# ControlPCB_14042025.net
KiCad netlist of a schematic drawn in EAGLE
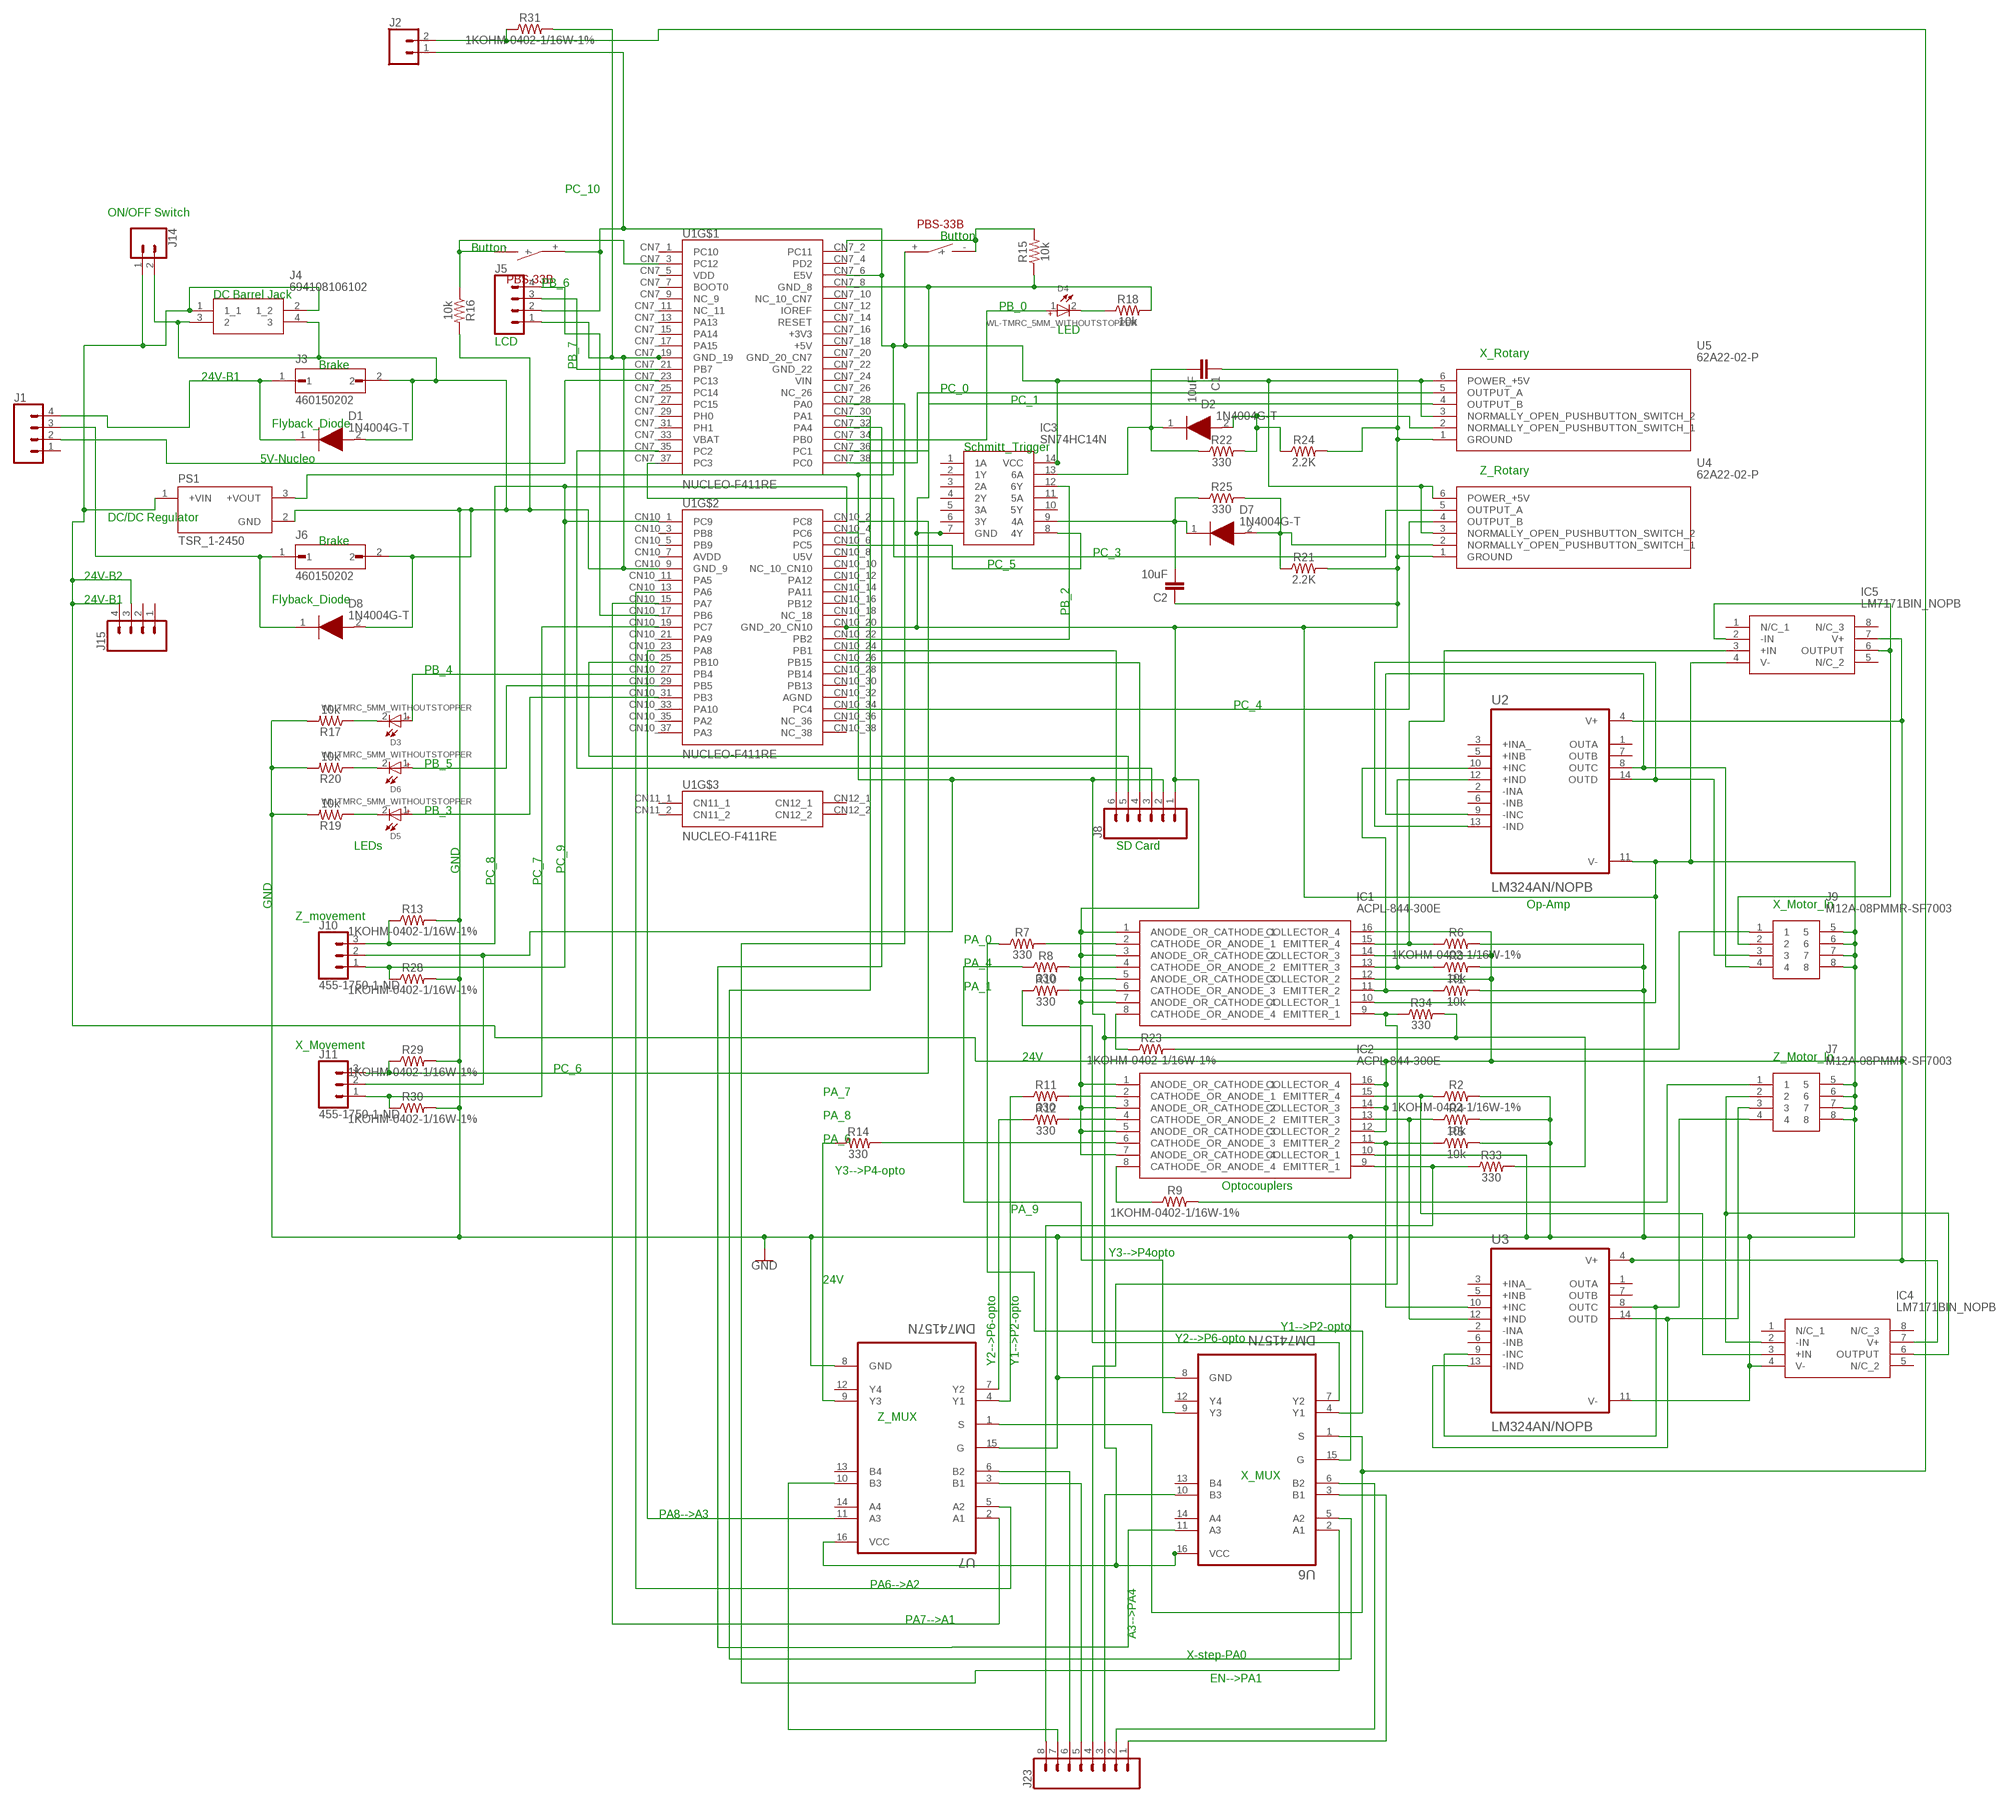
[diagram p0: schematic, sheet 1]

(export (version "E")
  (design (tool "Eeschema 10.0.6"))
  (components
    (comp (ref "C1")
      (value "10uF")
      (footprint "eagle-import:0603")
      (libsource (lib "eagle-import") (part "10UF-0603-6.3V-20%"))
    )
    (comp (ref "C2")
      (value "10uF")
      (footprint "eagle-import:0603")
      (libsource (lib "eagle-import") (part "10UF-0603-6.3V-20%"))
    )
    (comp (ref "D1")
      (value "1N4004G-T")
      (footprint "eagle-import:DIOAD1408W86L464D236")
      (fields (field (name "MOUSER_PART_NUMBER") "621-1N4004G-T"))
      (libsource (lib "eagle-import") (part "1N4004G-T"))
    )
    (comp (ref "D2")
      (value "1N4004G-T")
      (footprint "eagle-import:DIOAD1408W86L464D236")
      (fields (field (name "MOUSER_PART_NUMBER") "621-1N4004G-T"))
      (libsource (lib "eagle-import") (part "1N4004G-T"))
    )
    (comp (ref "D3")
      (value "WL-TMRC_5MM_WITHOUTSTOPPER")
      (footprint "eagle-import:WL-TMRC_5MM")
      (libsource (lib "eagle-import") (part "WL-TMRC_5MM_WITHOUTSTOPPER"))
    )
    (comp (ref "D4")
      (value "WL-TMRC_5MM_WITHOUTSTOPPER")
      (footprint "eagle-import:WL-TMRC_5MM")
      (libsource (lib "eagle-import") (part "WL-TMRC_5MM_WITHOUTSTOPPER"))
    )
    (comp (ref "D5")
      (value "WL-TMRC_5MM_WITHOUTSTOPPER")
      (footprint "eagle-import:WL-TMRC_5MM")
      (libsource (lib "eagle-import") (part "WL-TMRC_5MM_WITHOUTSTOPPER"))
    )
    (comp (ref "D6")
      (value "WL-TMRC_5MM_WITHOUTSTOPPER")
      (footprint "eagle-import:WL-TMRC_5MM")
      (libsource (lib "eagle-import") (part "WL-TMRC_5MM_WITHOUTSTOPPER"))
    )
    (comp (ref "D7")
      (value "1N4004G-T")
      (footprint "eagle-import:DIOAD1408W86L464D236")
      (fields (field (name "MOUSER_PART_NUMBER") "621-1N4004G-T"))
      (libsource (lib "eagle-import") (part "1N4004G-T"))
    )
    (comp (ref "D8")
      (value "1N4004G-T")
      (footprint "eagle-import:DIOAD1408W86L464D236")
      (fields (field (name "MOUSER_PART_NUMBER") "621-1N4004G-T"))
      (libsource (lib "eagle-import") (part "1N4004G-T"))
    )
    (comp (ref "IC1")
      (value "ACPL-844-300E")
      (footprint "eagle-import:DIP880W60P254L1984H450Q16N")
      (fields (field (name "MOUSER_PART_NUMBER") "630-ACPL-844-300E"))
      (libsource (lib "eagle-import") (part "ACPL-844-300E"))
    )
    (comp (ref "IC2")
      (value "ACPL-844-300E")
      (footprint "eagle-import:DIP880W60P254L1984H450Q16N")
      (fields (field (name "MOUSER_PART_NUMBER") "630-ACPL-844-300E"))
      (libsource (lib "eagle-import") (part "ACPL-844-300E"))
    )
    (comp (ref "IC3")
      (value "SN74HC14N")
      (footprint "eagle-import:DIP794W53P254L1930H508Q14N")
      (fields (field (name "MOUSER_PART_NUMBER") "595-SN74HC14N"))
      (libsource (lib "eagle-import") (part "SN74HC14N"))
    )
    (comp (ref "IC4")
      (value "LM7171BIN_NOPB")
      (footprint "eagle-import:DIP794W53P254L959H508Q8N")
      (fields
        (field (name "ARROW_PART_NUMBER") "LM7171BIN/NOPB")
        (field (name "MOUSER_PART_NUMBER") "926-LM7171BIN/NOPB")
      )
      (libsource (lib "eagle-import") (part "LM7171BIN_NOPB"))
    )
    (comp (ref "IC5")
      (value "LM7171BIN_NOPB")
      (footprint "eagle-import:DIP794W53P254L959H508Q8N")
      (fields
        (field (name "ARROW_PART_NUMBER") "LM7171BIN/NOPB")
        (field (name "MOUSER_PART_NUMBER") "926-LM7171BIN/NOPB")
      )
      (libsource (lib "eagle-import") (part "LM7171BIN_NOPB"))
    )
    (comp (ref "J1")
      (value "CONN_04PTH")
      (footprint "eagle-import:1X04")
      (libsource (lib "eagle-import") (part "CONN_04PTH"))
    )
    (comp (ref "J2")
      (value "CONN_02")
      (footprint "eagle-import:1X02")
      (libsource (lib "eagle-import") (part "CONN_02"))
    )
    (comp (ref "J3")
      (value "460150202")
      (footprint "eagle-import:MOLEX_460150202")
      (fields (field (name "MANUFACTURER") "Molex"))
      (libsource (lib "eagle-import") (part "460150202"))
    )
    (comp (ref "J4")
      (value "694108106102")
      (footprint "eagle-import:694108106102")
      (fields (field (name "MOUSER_PART_NUMBER") "710-694108106102"))
      (libsource (lib "eagle-import") (part "694108106102"))
    )
    (comp (ref "J5")
      (value "CONN_04LOCK")
      (footprint "eagle-import:1X04_LOCK")
      (libsource (lib "eagle-import") (part "CONN_04LOCK"))
    )
    (comp (ref "J6")
      (value "460150202")
      (footprint "eagle-import:MOLEX_460150202")
      (fields (field (name "MANUFACTURER") "Molex"))
      (libsource (lib "eagle-import") (part "460150202"))
    )
    (comp (ref "J7")
      (value "M12A-08PMMR-SF7003")
      (footprint "eagle-import:M12A08PMMRSF7003")
      (fields (field (name "MOUSER_PART_NUMBER") "523-M12A08PMMRSF7003"))
      (libsource (lib "eagle-import") (part "M12A-08PMMR-SF7003"))
    )
    (comp (ref "J8")
      (value "CONN_06SILK_FEMALE_PTH")
      (footprint "eagle-import:1X06")
      (libsource (lib "eagle-import") (part "CONN_06SILK_FEMALE_PTH"))
    )
    (comp (ref "J9")
      (value "M12A-08PMMR-SF7003")
      (footprint "eagle-import:M12A08PMMRSF7003")
      (fields (field (name "MOUSER_PART_NUMBER") "523-M12A08PMMRSF7003"))
      (libsource (lib "eagle-import") (part "M12A-08PMMR-SF7003"))
    )
    (comp (ref "J10")
      (value "455-1750-1-ND")
      (footprint "eagle-import:1X03")
      (libsource (lib "eagle-import") (part "CONN_03"))
    )
    (comp (ref "J11")
      (value "455-1750-1-ND")
      (footprint "eagle-import:1X03")
      (libsource (lib "eagle-import") (part "CONN_03"))
    )
    (comp (ref "J14")
      (value "CONN_02")
      (footprint "eagle-import:1X02")
      (libsource (lib "eagle-import") (part "CONN_02"))
    )
    (comp (ref "J15")
      (value "CONN_04PTH")
      (footprint "eagle-import:1X04")
      (libsource (lib "eagle-import") (part "CONN_04PTH"))
    )
    (comp (ref "J23")
      (value "CONN_08\"")
      (footprint "eagle-import:1X08")
      (libsource (lib "eagle-import") (part "CONN_08{dblquote}"))
    )
    (comp (ref "PS1")
      (value "TSR_1-2450")
      (footprint "eagle-import:CONV_TSR_1-2450")
      (fields (field (name "MANUFACTURER") "Traco Power"))
      (libsource (lib "eagle-import") (part "TSR_1-2450"))
    )
    (comp (ref "R1")
      (value "10k")
      (footprint "eagle-import:0402")
      (libsource (lib "eagle-import") (part "10KOHM-0402-1/16W-1%"))
    )
    (comp (ref "R2")
      (value "1KOHM-0402-1/16W-1%")
      (footprint "eagle-import:0402")
      (libsource (lib "eagle-import") (part "1KOHM-0402-1/16W-1%"))
    )
    (comp (ref "R3")
      (value "10k")
      (footprint "eagle-import:0402")
      (libsource (lib "eagle-import") (part "10KOHM-0402-1/16W-1%"))
    )
    (comp (ref "R4")
      (value "10k")
      (footprint "eagle-import:0402")
      (libsource (lib "eagle-import") (part "10KOHM-0402-1/16W-1%"))
    )
    (comp (ref "R5")
      (value "10k")
      (footprint "eagle-import:0402")
      (libsource (lib "eagle-import") (part "10KOHM-0402-1/16W-1%"))
    )
    (comp (ref "R6")
      (value "1KOHM-0402-1/16W-1%")
      (footprint "eagle-import:0402")
      (libsource (lib "eagle-import") (part "1KOHM-0402-1/16W-1%"))
    )
    (comp (ref "R7")
      (value "330")
      (footprint "eagle-import:0402")
      (libsource (lib "eagle-import") (part "330OHM-0402-1/16W-5%"))
    )
    (comp (ref "R8")
      (value "330")
      (footprint "eagle-import:0402")
      (libsource (lib "eagle-import") (part "330OHM-0402-1/16W-5%"))
    )
    (comp (ref "R9")
      (value "1KOHM-0402-1/16W-1%")
      (footprint "eagle-import:0402")
      (libsource (lib "eagle-import") (part "1KOHM-0402-1/16W-1%"))
    )
    (comp (ref "R10")
      (value "330")
      (footprint "eagle-import:0402")
      (libsource (lib "eagle-import") (part "330OHM-0402-1/16W-5%"))
    )
    (comp (ref "R11")
      (value "330")
      (footprint "eagle-import:0402")
      (libsource (lib "eagle-import") (part "330OHM-0402-1/16W-5%"))
    )
    (comp (ref "R12")
      (value "330")
      (footprint "eagle-import:0402")
      (libsource (lib "eagle-import") (part "330OHM-0402-1/16W-5%"))
    )
    (comp (ref "R13")
      (value "1KOHM-0402-1/16W-1%")
      (footprint "eagle-import:0402")
      (libsource (lib "eagle-import") (part "1KOHM-0402-1/16W-1%"))
    )
    (comp (ref "R14")
      (value "330")
      (footprint "eagle-import:0402")
      (libsource (lib "eagle-import") (part "330OHM-0402-1/16W-5%"))
    )
    (comp (ref "R15")
      (value "10k")
      (footprint "eagle-import:0402")
      (libsource (lib "eagle-import") (part "10KOHM-0402-1/16W-1%"))
    )
    (comp (ref "R16")
      (value "10k")
      (footprint "eagle-import:0402")
      (libsource (lib "eagle-import") (part "10KOHM-0402-1/16W-1%"))
    )
    (comp (ref "R17")
      (value "10k")
      (footprint "eagle-import:0402")
      (libsource (lib "eagle-import") (part "10KOHM-0402-1/16W-1%"))
    )
    (comp (ref "R18")
      (value "10k")
      (footprint "eagle-import:0402")
      (libsource (lib "eagle-import") (part "10KOHM-0402-1/16W-1%"))
    )
    (comp (ref "R19")
      (value "10k")
      (footprint "eagle-import:0402")
      (libsource (lib "eagle-import") (part "10KOHM-0402-1/16W-1%"))
    )
    (comp (ref "R20")
      (value "10k")
      (footprint "eagle-import:0402")
      (libsource (lib "eagle-import") (part "10KOHM-0402-1/16W-1%"))
    )
    (comp (ref "R21")
      (value "2.2K")
      (footprint "eagle-import:0402")
      (libsource (lib "eagle-import") (part "2.2KOHM-0402-1/16W-1%"))
    )
    (comp (ref "R22")
      (value "330")
      (footprint "eagle-import:0402")
      (libsource (lib "eagle-import") (part "330OHM-0402-1/16W-5%"))
    )
    (comp (ref "R23")
      (value "1KOHM-0402-1/16W-1%")
      (footprint "eagle-import:0402")
      (libsource (lib "eagle-import") (part "1KOHM-0402-1/16W-1%"))
    )
    (comp (ref "R24")
      (value "2.2K")
      (footprint "eagle-import:0402")
      (libsource (lib "eagle-import") (part "2.2KOHM-0402-1/16W-1%"))
    )
    (comp (ref "R25")
      (value "330")
      (footprint "eagle-import:0402")
      (libsource (lib "eagle-import") (part "330OHM-0402-1/16W-5%"))
    )
    (comp (ref "R28")
      (value "1KOHM-0402-1/16W-1%")
      (footprint "eagle-import:0402")
      (libsource (lib "eagle-import") (part "1KOHM-0402-1/16W-1%"))
    )
    (comp (ref "R29")
      (value "1KOHM-0402-1/16W-1%")
      (footprint "eagle-import:0402")
      (libsource (lib "eagle-import") (part "1KOHM-0402-1/16W-1%"))
    )
    (comp (ref "R30")
      (value "1KOHM-0402-1/16W-1%")
      (footprint "eagle-import:0402")
      (libsource (lib "eagle-import") (part "1KOHM-0402-1/16W-1%"))
    )
    (comp (ref "R31")
      (value "1KOHM-0402-1/16W-1%")
      (footprint "eagle-import:0402")
      (libsource (lib "eagle-import") (part "1KOHM-0402-1/16W-1%"))
    )
    (comp (ref "R33")
      (value "330")
      (footprint "eagle-import:0402")
      (libsource (lib "eagle-import") (part "330OHM-0402-1/16W-5%"))
    )
    (comp (ref "R34")
      (value "330")
      (footprint "eagle-import:0402")
      (libsource (lib "eagle-import") (part "330OHM-0402-1/16W-5%"))
    )
    (comp (ref "U$1")
      (value "PBS-33B")
      (footprint "eagle-import:PBS-33B")
      (libsource (lib "eagle-import") (part "PBS-33B"))
    )
    (comp (ref "U$2")
      (value "PBS-33B")
      (footprint "eagle-import:PBS-33B")
      (libsource (lib "eagle-import") (part "PBS-33B"))
    )
    (comp (ref "U1")
      (value "NUCLEO-F411RE")
      (footprint "eagle-import:BOARD_NUCLEO-F411RE")
      (fields (field (name "DIGIKEY_PART_NUMBER") "497-14711-ND") (field (name "MF") "STMicroelectronics"))
      (libsource (lib "eagle-import") (part "NUCLEO-F411RE"))
    )
    (comp (ref "U2")
      (value "LM324AN/NOPB")
      (footprint "eagle-import:DIP794W45P254L1969H508Q14")
      (libsource (lib "eagle-import") (part "LM324AN/NOPB"))
    )
    (comp (ref "U3")
      (value "LM324AN/NOPB")
      (footprint "eagle-import:DIP794W45P254L1969H508Q14")
      (libsource (lib "eagle-import") (part "LM324AN/NOPB"))
    )
    (comp (ref "U4")
      (value "62A22-02-P")
      (footprint "eagle-import:62A2202P")
      (fields (field (name "MOUSER_PART_NUMBER") "706-62A22-02-P"))
      (libsource (lib "eagle-import") (part "62A22-02-P"))
    )
    (comp (ref "U5")
      (value "62A22-02-P")
      (footprint "eagle-import:62A2202P")
      (fields (field (name "MOUSER_PART_NUMBER") "706-62A22-02-P"))
      (libsource (lib "eagle-import") (part "62A22-02-P"))
    )
    (comp (ref "U6")
      (value "DM74157N")
      (footprint "eagle-import:DIP794W45P254L1918H533Q16")
      (fields (field (name "MF") "ON Semiconductor"))
      (libsource (lib "eagle-import") (part "DM74157N"))
    )
    (comp (ref "U7")
      (value "DM74157N")
      (footprint "eagle-import:DIP794W45P254L1918H533Q16")
      (fields (field (name "MF") "ON Semiconductor"))
      (libsource (lib "eagle-import") (part "DM74157N"))
    )
  )
  (nets
    (net (code "1") (name "/+3V3") (class "Default")
      (node (ref "U1") (pin "CN7_16") (pinfunction "+3V3_CN7_16") (pintype "power_in"))
    )
    (net (code "2") (name "/+5V") (class "Default")
      (node (ref "U1") (pin "CN7_18") (pinfunction "+5V_CN7_18") (pintype "power_in"))
    )
    (net (code "3") (name "/AGND") (class "Default")
      (node (ref "U1") (pin "CN10_32") (pinfunction "AGND_CN10_32") (pintype "power_in"))
    )
    (net (code "4") (name "/AVDD") (class "Default")
      (node (ref "U1") (pin "CN10_7") (pinfunction "AVDD_CN10_7") (pintype "power_in"))
    )
    (net (code "5") (name "/GND_20_CN7") (class "Default")
      (node (ref "U1") (pin "CN7_20") (pinfunction "GND_20_CN7_CN7_20") (pintype "power_in"))
    )
    (net (code "6") (name "/GND_22") (class "Default")
      (node (ref "U1") (pin "CN7_22") (pinfunction "GND_22_CN7_22") (pintype "power_in"))
    )
    (net (code "7") (name "/U5V") (class "Default")
      (node (ref "U1") (pin "CN10_8") (pinfunction "U5V_CN10_8") (pintype "power_in"))
    )
    (net (code "8") (name "/VBAT") (class "Default")
      (node (ref "U1") (pin "CN7_33") (pinfunction "VBAT_CN7_33") (pintype "power_in"))
    )
    (net (code "9") (name "/VDD") (class "Default")
      (node (ref "U1") (pin "CN7_5") (pinfunction "VDD_CN7_5") (pintype "power_in"))
    )
    (net (code "10") (name "GND") (class "Default")
      (node (ref "C1") (pin "1") (pinfunction "1_1") (pintype "passive"))
      (node (ref "C2") (pin "1") (pinfunction "1_1") (pintype "passive"))
      (node (ref "D1") (pin "2") (pinfunction "A_2") (pintype "bidirectional"))
      (node (ref "D8") (pin "2") (pinfunction "A_2") (pintype "bidirectional"))
      (node (ref "IC1") (pin "1") (pinfunction "ANODE_OR_CATHODE_1_1") (pintype "bidirectional"))
      (node (ref "IC1") (pin "10") (pinfunction "COLLECTOR_1_10") (pintype "bidirectional"))
      (node (ref "IC1") (pin "3") (pinfunction "ANODE_OR_CATHODE_2_3") (pintype "bidirectional"))
      (node (ref "IC1") (pin "5") (pinfunction "ANODE_OR_CATHODE_3_5") (pintype "bidirectional"))
      (node (ref "IC1") (pin "7") (pinfunction "ANODE_OR_CATHODE_4_7") (pintype "bidirectional"))
      (node (ref "IC2") (pin "1") (pinfunction "ANODE_OR_CATHODE_1_1") (pintype "bidirectional"))
      (node (ref "IC2") (pin "10") (pinfunction "COLLECTOR_1_10") (pintype "bidirectional"))
      (node (ref "IC2") (pin "3") (pinfunction "ANODE_OR_CATHODE_2_3") (pintype "bidirectional"))
      (node (ref "IC2") (pin "5") (pinfunction "ANODE_OR_CATHODE_3_5") (pintype "bidirectional"))
      (node (ref "IC2") (pin "7") (pinfunction "ANODE_OR_CATHODE_4_7") (pintype "bidirectional"))
      (node (ref "IC3") (pin "7") (pinfunction "GND_7") (pintype "bidirectional"))
      (node (ref "IC4") (pin "4") (pinfunction "V-_4") (pintype "bidirectional"))
      (node (ref "IC5") (pin "4") (pinfunction "V-_4") (pintype "bidirectional"))
      (node (ref "J14") (pin "2") (pinfunction "2_2") (pintype "passive"))
      (node (ref "J3") (pin "2") (pinfunction "2_2") (pintype "passive"))
      (node (ref "J4") (pin "3") (pinfunction "2_3") (pintype "bidirectional"))
      (node (ref "J4") (pin "4") (pinfunction "3_4") (pintype "bidirectional"))
      (node (ref "J5") (pin "1") (pinfunction "1_1") (pintype "passive"))
      (node (ref "J6") (pin "2") (pinfunction "2_2") (pintype "passive"))
      (node (ref "J7") (pin "5") (pinfunction "5_5") (pintype "bidirectional"))
      (node (ref "J7") (pin "6") (pinfunction "6_6") (pintype "bidirectional"))
      (node (ref "J7") (pin "7") (pinfunction "7_7") (pintype "bidirectional"))
      (node (ref "J7") (pin "8") (pinfunction "8_8") (pintype "bidirectional"))
      (node (ref "J8") (pin "1") (pinfunction "1_1") (pintype "passive"))
      (node (ref "J9") (pin "5") (pinfunction "5_5") (pintype "bidirectional"))
      (node (ref "J9") (pin "6") (pinfunction "6_6") (pintype "bidirectional"))
      (node (ref "J9") (pin "7") (pinfunction "7_7") (pintype "bidirectional"))
      (node (ref "J9") (pin "8") (pinfunction "8_8") (pintype "bidirectional"))
      (node (ref "PS1") (pin "2") (pinfunction "GND_2") (pintype "power_in"))
      (node (ref "R1") (pin "2") (pinfunction "2_2") (pintype "passive"))
      (node (ref "R13") (pin "2") (pinfunction "2_2") (pintype "passive"))
      (node (ref "R15") (pin "1") (pinfunction "1_1") (pintype "passive"))
      (node (ref "R16") (pin "2") (pinfunction "2_2") (pintype "passive"))
      (node (ref "R17") (pin "2") (pinfunction "2_2") (pintype "passive"))
      (node (ref "R18") (pin "2") (pinfunction "2_2") (pintype "passive"))
      (node (ref "R19") (pin "2") (pinfunction "2_2") (pintype "passive"))
      (node (ref "R2") (pin "2") (pinfunction "2_2") (pintype "passive"))
      (node (ref "R20") (pin "2") (pinfunction "2_2") (pintype "passive"))
      (node (ref "R21") (pin "2") (pinfunction "2_2") (pintype "passive"))
      (node (ref "R24") (pin "2") (pinfunction "2_2") (pintype "passive"))
      (node (ref "R28") (pin "2") (pinfunction "2_2") (pintype "passive"))
      (node (ref "R29") (pin "2") (pinfunction "2_2") (pintype "passive"))
      (node (ref "R3") (pin "2") (pinfunction "2_2") (pintype "passive"))
      (node (ref "R30") (pin "2") (pinfunction "2_2") (pintype "passive"))
      (node (ref "R31") (pin "2") (pinfunction "2_2") (pintype "passive"))
      (node (ref "R4") (pin "2") (pinfunction "2_2") (pintype "passive"))
      (node (ref "R5") (pin "2") (pinfunction "2_2") (pintype "passive"))
      (node (ref "R6") (pin "2") (pinfunction "2_2") (pintype "passive"))
      (node (ref "U1") (pin "CN10_20") (pinfunction "GND_20_CN10_CN10_20") (pintype "power_in"))
      (node (ref "U1") (pin "CN10_9") (pinfunction "GND_9_CN10_9") (pintype "power_in"))
      (node (ref "U1") (pin "CN7_19") (pinfunction "GND_19_CN7_19") (pintype "power_in"))
      (node (ref "U1") (pin "CN7_8") (pinfunction "GND_8_CN7_8") (pintype "power_in"))
      (node (ref "U2") (pin "11") (pinfunction "V-_11") (pintype "power_in"))
      (node (ref "U3") (pin "11") (pinfunction "V-_11") (pintype "power_in"))
      (node (ref "U4") (pin "1") (pinfunction "GROUND_1") (pintype "bidirectional"))
      (node (ref "U5") (pin "1") (pinfunction "GROUND_1") (pintype "bidirectional"))
      (node (ref "U6") (pin "15") (pinfunction "G_15") (pintype "bidirectional"))
      (node (ref "U6") (pin "8") (pinfunction "GND_8") (pintype "power_in"))
      (node (ref "U7") (pin "15") (pinfunction "G_15") (pintype "bidirectional"))
      (node (ref "U7") (pin "8") (pinfunction "GND_8") (pintype "power_in"))
    )
    (net (code "11") (name "Net-(D1-K)") (class "Default")
      (node (ref "D1") (pin "1") (pinfunction "K_1") (pintype "bidirectional"))
      (node (ref "J1") (pin "4") (pinfunction "4_4") (pintype "passive"))
      (node (ref "J3") (pin "1") (pinfunction "1_1") (pintype "passive"))
    )
    (net (code "12") (name "Net-(D2-A)") (class "Default")
      (node (ref "D2") (pin "2") (pinfunction "A_2") (pintype "bidirectional"))
      (node (ref "R22") (pin "2") (pinfunction "2_2") (pintype "passive"))
      (node (ref "R24") (pin "1") (pinfunction "1_1") (pintype "passive"))
      (node (ref "U5") (pin "2") (pinfunction "NORMALLY_OPEN_PUSHBUTTON_SWITCH_1_2") (pintype "bidirectional"))
    )
    (net (code "13") (name "Net-(D2-K)") (class "Default")
      (node (ref "C1") (pin "2") (pinfunction "2_2") (pintype "passive"))
      (node (ref "D2") (pin "1") (pinfunction "K_1") (pintype "bidirectional"))
      (node (ref "IC3") (pin "13") (pinfunction "6A_13") (pintype "bidirectional"))
      (node (ref "R22") (pin "1") (pinfunction "1_1") (pintype "passive"))
    )
    (net (code "14") (name "Net-(D3-+)") (class "Default")
      (node (ref "D3") (pin "1") (pinfunction "+_1") (pintype "passive"))
      (node (ref "U1") (pin "CN10_27") (pinfunction "PB4_CN10_27") (pintype "bidirectional"))
    )
    (net (code "15") (name "Net-(D3--)") (class "Default")
      (node (ref "D3") (pin "2") (pinfunction "-_2") (pintype "passive"))
      (node (ref "R17") (pin "1") (pinfunction "1_1") (pintype "passive"))
    )
    (net (code "16") (name "Net-(D4-+)") (class "Default")
      (node (ref "D4") (pin "1") (pinfunction "+_1") (pintype "passive"))
      (node (ref "U1") (pin "CN7_34") (pinfunction "PB0_CN7_34") (pintype "bidirectional"))
    )
    (net (code "17") (name "Net-(D4--)") (class "Default")
      (node (ref "D4") (pin "2") (pinfunction "-_2") (pintype "passive"))
      (node (ref "R18") (pin "1") (pinfunction "1_1") (pintype "passive"))
    )
    (net (code "18") (name "Net-(D5-+)") (class "Default")
      (node (ref "D5") (pin "1") (pinfunction "+_1") (pintype "passive"))
      (node (ref "U1") (pin "CN10_31") (pinfunction "PB3_CN10_31") (pintype "bidirectional"))
    )
    (net (code "19") (name "Net-(D5--)") (class "Default")
      (node (ref "D5") (pin "2") (pinfunction "-_2") (pintype "passive"))
      (node (ref "R19") (pin "1") (pinfunction "1_1") (pintype "passive"))
    )
    (net (code "20") (name "Net-(D6-+)") (class "Default")
      (node (ref "D6") (pin "1") (pinfunction "+_1") (pintype "passive"))
      (node (ref "U1") (pin "CN10_29") (pinfunction "PB5_CN10_29") (pintype "bidirectional"))
    )
    (net (code "21") (name "Net-(D6--)") (class "Default")
      (node (ref "D6") (pin "2") (pinfunction "-_2") (pintype "passive"))
      (node (ref "R20") (pin "1") (pinfunction "1_1") (pintype "passive"))
    )
    (net (code "22") (name "Net-(D7-A)") (class "Default")
      (node (ref "D7") (pin "2") (pinfunction "A_2") (pintype "bidirectional"))
      (node (ref "R21") (pin "1") (pinfunction "1_1") (pintype "passive"))
      (node (ref "R25") (pin "2") (pinfunction "2_2") (pintype "passive"))
      (node (ref "U4") (pin "2") (pinfunction "NORMALLY_OPEN_PUSHBUTTON_SWITCH_1_2") (pintype "bidirectional"))
    )
    (net (code "23") (name "Net-(D7-K)") (class "Default")
      (node (ref "C2") (pin "2") (pinfunction "2_2") (pintype "passive"))
      (node (ref "D7") (pin "1") (pinfunction "K_1") (pintype "bidirectional"))
      (node (ref "IC3") (pin "9") (pinfunction "4A_9") (pintype "bidirectional"))
      (node (ref "R25") (pin "1") (pinfunction "1_1") (pintype "passive"))
    )
    (net (code "24") (name "Net-(D8-K)") (class "Default")
      (node (ref "D8") (pin "1") (pinfunction "K_1") (pintype "bidirectional"))
      (node (ref "J1") (pin "3") (pinfunction "3_3") (pintype "passive"))
      (node (ref "J6") (pin "1") (pinfunction "1_1") (pintype "passive"))
    )
    (net (code "25") (name "Net-(IC1-CATHODE_OR_ANODE_1)") (class "Default")
      (node (ref "IC1") (pin "2") (pinfunction "CATHODE_OR_ANODE_1_2") (pintype "bidirectional"))
      (node (ref "R7") (pin "2") (pinfunction "2_2") (pintype "passive"))
    )
    (net (code "26") (name "Net-(IC1-CATHODE_OR_ANODE_2)") (class "Default")
      (node (ref "IC1") (pin "4") (pinfunction "CATHODE_OR_ANODE_2_4") (pintype "bidirectional"))
      (node (ref "R8") (pin "2") (pinfunction "2_2") (pintype "passive"))
    )
    (net (code "27") (name "Net-(IC1-CATHODE_OR_ANODE_3)") (class "Default")
      (node (ref "IC1") (pin "6") (pinfunction "CATHODE_OR_ANODE_3_6") (pintype "bidirectional"))
      (node (ref "R10") (pin "2") (pinfunction "2_2") (pintype "passive"))
    )
    (net (code "28") (name "Net-(IC1-CATHODE_OR_ANODE_4)") (class "Default")
      (node (ref "IC1") (pin "8") (pinfunction "CATHODE_OR_ANODE_4_8") (pintype "bidirectional"))
      (node (ref "R23") (pin "1") (pinfunction "1_1") (pintype "passive"))
    )
    (net (code "29") (name "Net-(IC1-COLLECTOR_2)") (class "Default")
      (node (ref "IC1") (pin "12") (pinfunction "COLLECTOR_2_12") (pintype "bidirectional"))
      (node (ref "IC1") (pin "14") (pinfunction "COLLECTOR_3_14") (pintype "bidirectional"))
      (node (ref "IC1") (pin "16") (pinfunction "COLLECTOR_4_16") (pintype "bidirectional"))
      (node (ref "IC2") (pin "12") (pinfunction "COLLECTOR_2_12") (pintype "bidirectional"))
      (node (ref "IC2") (pin "14") (pinfunction "COLLECTOR_3_14") (pintype "bidirectional"))
      (node (ref "IC2") (pin "16") (pinfunction "COLLECTOR_4_16") (pintype "bidirectional"))
      (node (ref "IC4") (pin "7") (pinfunction "V+_7") (pintype "bidirectional"))
      (node (ref "IC5") (pin "7") (pinfunction "V+_7") (pintype "bidirectional"))
      (node (ref "J14") (pin "1") (pinfunction "1_1") (pintype "passive"))
      (node (ref "J15") (pin "3") (pinfunction "3_3") (pintype "passive"))
      (node (ref "J15") (pin "4") (pinfunction "4_4") (pintype "passive"))
      (node (ref "J4") (pin "1") (pinfunction "1_1_1") (pintype "bidirectional"))
      (node (ref "J4") (pin "2") (pinfunction "1_2_2") (pintype "bidirectional"))
      (node (ref "PS1") (pin "1") (pinfunction "+VIN_1") (pintype "input"))
      (node (ref "U2") (pin "4") (pinfunction "V+_4") (pintype "power_in"))
      (node (ref "U3") (pin "4") (pinfunction "V+_4") (pintype "power_in"))
    )
    (net (code "30") (name "Net-(IC1-EMITTER_1)") (class "Default")
      (node (ref "IC1") (pin "9") (pinfunction "EMITTER_1_9") (pintype "bidirectional"))
      (node (ref "J23") (pin "4") (pinfunction "4_4") (pintype "passive"))
      (node (ref "R34") (pin "1") (pinfunction "1_1") (pintype "passive"))
    )
    (net (code "31") (name "Net-(IC1-EMITTER_2)") (class "Default")
      (node (ref "IC1") (pin "11") (pinfunction "EMITTER_2_11") (pintype "bidirectional"))
      (node (ref "R1") (pin "1") (pinfunction "1_1") (pintype "passive"))
      (node (ref "U2") (pin "10") (pinfunction "+INC_10") (pintype "input"))
    )
    (net (code "32") (name "Net-(IC1-EMITTER_3)") (class "Default")
      (node (ref "IC1") (pin "13") (pinfunction "EMITTER_3_13") (pintype "bidirectional"))
      (node (ref "R3") (pin "1") (pinfunction "1_1") (pintype "passive"))
      (node (ref "U2") (pin "12") (pinfunction "+IND_12") (pintype "input"))
    )
    (net (code "33") (name "Net-(IC1-EMITTER_4)") (class "Default")
      (node (ref "IC1") (pin "15") (pinfunction "EMITTER_4_15") (pintype "bidirectional"))
      (node (ref "IC5") (pin "3") (pinfunction "+IN_3") (pintype "bidirectional"))
      (node (ref "R6") (pin "1") (pinfunction "1_1") (pintype "passive"))
    )
    (net (code "34") (name "Net-(IC2-CATHODE_OR_ANODE_1)") (class "Default")
      (node (ref "IC2") (pin "2") (pinfunction "CATHODE_OR_ANODE_1_2") (pintype "bidirectional"))
      (node (ref "R11") (pin "2") (pinfunction "2_2") (pintype "passive"))
    )
    (net (code "35") (name "Net-(IC2-CATHODE_OR_ANODE_2)") (class "Default")
      (node (ref "IC2") (pin "4") (pinfunction "CATHODE_OR_ANODE_2_4") (pintype "bidirectional"))
      (node (ref "R12") (pin "2") (pinfunction "2_2") (pintype "passive"))
    )
    (net (code "36") (name "Net-(IC2-CATHODE_OR_ANODE_3)") (class "Default")
      (node (ref "IC2") (pin "6") (pinfunction "CATHODE_OR_ANODE_3_6") (pintype "bidirectional"))
      (node (ref "R14") (pin "2") (pinfunction "2_2") (pintype "passive"))
    )
    (net (code "37") (name "Net-(IC2-CATHODE_OR_ANODE_4)") (class "Default")
      (node (ref "IC2") (pin "8") (pinfunction "CATHODE_OR_ANODE_4_8") (pintype "bidirectional"))
      (node (ref "R9") (pin "1") (pinfunction "1_1") (pintype "passive"))
    )
    (net (code "38") (name "Net-(IC2-EMITTER_1)") (class "Default")
      (node (ref "IC2") (pin "9") (pinfunction "EMITTER_1_9") (pintype "bidirectional"))
      (node (ref "J23") (pin "8") (pinfunction "8_8") (pintype "passive"))
      (node (ref "R33") (pin "1") (pinfunction "1_1") (pintype "passive"))
    )
    (net (code "39") (name "Net-(IC2-EMITTER_2)") (class "Default")
      (node (ref "IC2") (pin "11") (pinfunction "EMITTER_2_11") (pintype "bidirectional"))
      (node (ref "R5") (pin "1") (pinfunction "1_1") (pintype "passive"))
      (node (ref "U3") (pin "10") (pinfunction "+INC_10") (pintype "input"))
    )
    (net (code "40") (name "Net-(IC2-EMITTER_3)") (class "Default")
      (node (ref "IC2") (pin "13") (pinfunction "EMITTER_3_13") (pintype "bidirectional"))
      (node (ref "R4") (pin "1") (pinfunction "1_1") (pintype "passive"))
      (node (ref "U3") (pin "12") (pinfunction "+IND_12") (pintype "input"))
    )
    (net (code "41") (name "Net-(IC2-EMITTER_4)") (class "Default")
      (node (ref "IC2") (pin "15") (pinfunction "EMITTER_4_15") (pintype "bidirectional"))
      (node (ref "IC4") (pin "3") (pinfunction "+IN_3") (pintype "bidirectional"))
      (node (ref "R2") (pin "1") (pinfunction "1_1") (pintype "passive"))
    )
    (net (code "42") (name "Net-(IC3-4Y)") (class "Default")
      (node (ref "IC3") (pin "8") (pinfunction "4Y_8") (pintype "bidirectional"))
      (node (ref "U1") (pin "CN10_6") (pinfunction "PC5_CN10_6") (pintype "bidirectional"))
    )
    (net (code "43") (name "Net-(IC3-6Y)") (class "Default")
      (node (ref "IC3") (pin "12") (pinfunction "6Y_12") (pintype "bidirectional"))
      (node (ref "U1") (pin "CN10_22") (pinfunction "PB2_CN10_22") (pintype "bidirectional"))
    )
    (net (code "44") (name "Net-(IC3-VCC)") (class "Default")
      (node (ref "IC3") (pin "14") (pinfunction "VCC_14") (pintype "bidirectional"))
      (node (ref "J10") (pin "2") (pinfunction "2_2") (pintype "passive"))
      (node (ref "J11") (pin "2") (pinfunction "2_2") (pintype "passive"))
      (node (ref "J2") (pin "1") (pinfunction "1_1") (pintype "passive"))
      (node (ref "J5") (pin "2") (pinfunction "2_2") (pintype "passive"))
      (node (ref "J8") (pin "2") (pinfunction "2_2") (pintype "passive"))
      (node (ref "PS1") (pin "3") (pinfunction "+VOUT_3") (pintype "output"))
      (node (ref "R33") (pin "2") (pinfunction "2_2") (pintype "passive"))
      (node (ref "R34") (pin "2") (pinfunction "2_2") (pintype "passive"))
      (node (ref "U$1") (pin "+") (pinfunction "+_+") (pintype "bidirectional"))
      (node (ref "U$2") (pin "+") (pinfunction "+_+") (pintype "bidirectional"))
      (node (ref "U1") (pin "CN7_6") (pinfunction "E5V_CN7_6") (pintype "power_in"))
      (node (ref "U4") (pin "3") (pinfunction "NORMALLY_OPEN_PUSHBUTTON_SWITCH_2_3") (pintype "bidirectional"))
      (node (ref "U4") (pin "6") (pinfunction "POWER_+5V_6") (pintype "bidirectional"))
      (node (ref "U5") (pin "3") (pinfunction "NORMALLY_OPEN_PUSHBUTTON_SWITCH_2_3") (pintype "bidirectional"))
      (node (ref "U5") (pin "6") (pinfunction "POWER_+5V_6") (pintype "bidirectional"))
      (node (ref "U6") (pin "16") (pinfunction "VCC_16") (pintype "power_in"))
      (node (ref "U7") (pin "16") (pinfunction "VCC_16") (pintype "power_in"))
    )
    (net (code "45") (name "Net-(IC4--IN)") (class "Default")
      (node (ref "IC4") (pin "2") (pinfunction "-IN_2") (pintype "bidirectional"))
      (node (ref "IC4") (pin "6") (pinfunction "OUTPUT_6") (pintype "bidirectional"))
      (node (ref "J7") (pin "2") (pinfunction "2_2") (pintype "bidirectional"))
    )
    (net (code "46") (name "Net-(IC5--IN)") (class "Default")
      (node (ref "IC5") (pin "2") (pinfunction "-IN_2") (pintype "bidirectional"))
      (node (ref "IC5") (pin "6") (pinfunction "OUTPUT_6") (pintype "bidirectional"))
      (node (ref "J9") (pin "2") (pinfunction "2_2") (pintype "bidirectional"))
    )
    (net (code "47") (name "Net-(J7-Pad1)") (class "Default")
      (node (ref "J7") (pin "1") (pinfunction "1_1") (pintype "bidirectional"))
      (node (ref "R9") (pin "2") (pinfunction "2_2") (pintype "passive"))
    )
    (net (code "48") (name "Net-(J9-Pad1)") (class "Default")
      (node (ref "J9") (pin "1") (pinfunction "1_1") (pintype "bidirectional"))
      (node (ref "R23") (pin "2") (pinfunction "2_2") (pintype "passive"))
    )
    (net (code "49") (name "Net-(U1A-PA0)") (class "Default")
      (node (ref "U1") (pin "CN7_28") (pinfunction "PA0_CN7_28") (pintype "bidirectional"))
      (node (ref "U6") (pin "2") (pinfunction "A1_2") (pintype "bidirectional"))
    )
    (net (code "50") (name "Net-(U1A-PA1)") (class "Default")
      (node (ref "U1") (pin "CN7_30") (pinfunction "PA1_CN7_30") (pintype "bidirectional"))
      (node (ref "U6") (pin "5") (pinfunction "A2_5") (pintype "bidirectional"))
    )
    (net (code "51") (name "Net-(U1A-PA4)") (class "Default")
      (node (ref "U1") (pin "CN7_32") (pinfunction "PA4_CN7_32") (pintype "bidirectional"))
      (node (ref "U6") (pin "11") (pinfunction "A3_11") (pintype "bidirectional"))
    )
    (net (code "52") (name "Net-(U1A-PB7)") (class "Default")
      (node (ref "J5") (pin "3") (pinfunction "3_3") (pintype "passive"))
      (node (ref "U1") (pin "CN7_21") (pinfunction "PB7_CN7_21") (pintype "bidirectional"))
    )
    (net (code "53") (name "Net-(U1A-PC0)") (class "Default")
      (node (ref "U1") (pin "CN7_38") (pinfunction "PC0_CN7_38") (pintype "bidirectional"))
      (node (ref "U5") (pin "5") (pinfunction "OUTPUT_A_5") (pintype "bidirectional"))
    )
    (net (code "54") (name "Net-(U1A-PC1)") (class "Default")
      (node (ref "U1") (pin "CN7_36") (pinfunction "PC1_CN7_36") (pintype "bidirectional"))
      (node (ref "U5") (pin "4") (pinfunction "OUTPUT_B_4") (pintype "bidirectional"))
    )
    (net (code "55") (name "Net-(U1A-PC2)") (class "Default")
      (node (ref "J8") (pin "3") (pinfunction "3_3") (pintype "passive"))
      (node (ref "U1") (pin "CN7_35") (pinfunction "PC2_CN7_35") (pintype "bidirectional"))
    )
    (net (code "56") (name "Net-(U1A-PC3)") (class "Default")
      (node (ref "U1") (pin "CN7_37") (pinfunction "PC3_CN7_37") (pintype "bidirectional"))
      (node (ref "U4") (pin "5") (pinfunction "OUTPUT_A_5") (pintype "bidirectional"))
    )
    (net (code "57") (name "Net-(U1A-PC11)") (class "Default")
      (node (ref "R15") (pin "2") (pinfunction "2_2") (pintype "passive"))
      (node (ref "U$1") (pin "-") (pinfunction "-_-") (pintype "bidirectional"))
      (node (ref "U1") (pin "CN7_2") (pinfunction "PC11_CN7_2") (pintype "bidirectional"))
    )
    (net (code "58") (name "Net-(U1A-PC12)") (class "Default")
      (node (ref "R16") (pin "1") (pinfunction "1_1") (pintype "passive"))
      (node (ref "U$2") (pin "-") (pinfunction "-_-") (pintype "bidirectional"))
      (node (ref "U1") (pin "CN7_3") (pinfunction "PC12_CN7_3") (pintype "bidirectional"))
    )
    (net (code "59") (name "Net-(U1A-PC13)") (class "Default")
      (node (ref "J1") (pin "2") (pinfunction "2_2") (pintype "passive"))
      (node (ref "U1") (pin "CN7_23") (pinfunction "PC13_CN7_23") (pintype "bidirectional"))
    )
    (net (code "60") (name "Net-(U1B-PA6)") (class "Default")
      (node (ref "U1") (pin "CN10_13") (pinfunction "PA6_CN10_13") (pintype "bidirectional"))
      (node (ref "U7") (pin "5") (pinfunction "A2_5") (pintype "bidirectional"))
    )
    (net (code "61") (name "Net-(U1B-PA7)") (class "Default")
      (node (ref "U1") (pin "CN10_15") (pinfunction "PA7_CN10_15") (pintype "bidirectional"))
      (node (ref "U7") (pin "2") (pinfunction "A1_2") (pintype "bidirectional"))
    )
    (net (code "62") (name "Net-(U1B-PA8)") (class "Default")
      (node (ref "U1") (pin "CN10_23") (pinfunction "PA8_CN10_23") (pintype "bidirectional"))
      (node (ref "U7") (pin "11") (pinfunction "A3_11") (pintype "bidirectional"))
    )
    (net (code "63") (name "Net-(U1B-PB1)") (class "Default")
      (node (ref "J8") (pin "6") (pinfunction "6_6") (pintype "passive"))
      (node (ref "U1") (pin "CN10_24") (pinfunction "PB1_CN10_24") (pintype "bidirectional"))
    )
    (net (code "64") (name "Net-(U1B-PB6)") (class "Default")
      (node (ref "J5") (pin "4") (pinfunction "4_4") (pintype "passive"))
      (node (ref "U1") (pin "CN10_17") (pinfunction "PB6_CN10_17") (pintype "bidirectional"))
    )
    (net (code "65") (name "Net-(U1B-PB10)") (class "Default")
      (node (ref "J8") (pin "5") (pinfunction "5_5") (pintype "passive"))
      (node (ref "U1") (pin "CN10_25") (pinfunction "PB10_CN10_25") (pintype "bidirectional"))
    )
    (net (code "66") (name "Net-(U1B-PB15)") (class "Default")
      (node (ref "J8") (pin "4") (pinfunction "4_4") (pintype "passive"))
      (node (ref "U1") (pin "CN10_26") (pinfunction "PB15_CN10_26") (pintype "bidirectional"))
    )
    (net (code "67") (name "Net-(U1B-PC4)") (class "Default")
      (node (ref "U1") (pin "CN10_34") (pinfunction "PC4_CN10_34") (pintype "bidirectional"))
      (node (ref "U4") (pin "4") (pinfunction "OUTPUT_B_4") (pintype "bidirectional"))
    )
    (net (code "68") (name "Net-(U1B-PC6)") (class "Default")
      (node (ref "J11") (pin "3") (pinfunction "3_3") (pintype "passive"))
      (node (ref "R29") (pin "1") (pinfunction "1_1") (pintype "passive"))
      (node (ref "U1") (pin "CN10_4") (pinfunction "PC6_CN10_4") (pintype "bidirectional"))
    )
    (net (code "69") (name "Net-(U1B-PC7)") (class "Default")
      (node (ref "J11") (pin "1") (pinfunction "1_1") (pintype "passive"))
      (node (ref "R30") (pin "1") (pinfunction "1_1") (pintype "passive"))
      (node (ref "U1") (pin "CN10_19") (pinfunction "PC7_CN10_19") (pintype "bidirectional"))
    )
    (net (code "70") (name "Net-(U1B-PC8)") (class "Default")
      (node (ref "J10") (pin "1") (pinfunction "1_1") (pintype "passive"))
      (node (ref "J10") (pin "3") (pinfunction "3_3") (pintype "passive"))
      (node (ref "R13") (pin "1") (pinfunction "1_1") (pintype "passive"))
      (node (ref "R28") (pin "1") (pinfunction "1_1") (pintype "passive"))
      (node (ref "U1") (pin "CN10_1") (pinfunction "PC9_CN10_1") (pintype "bidirectional"))
      (node (ref "U1") (pin "CN10_2") (pinfunction "PC8_CN10_2") (pintype "bidirectional"))
    )
    (net (code "71") (name "Net-(U2--INC)") (class "Default")
      (node (ref "J9") (pin "4") (pinfunction "4_4") (pintype "bidirectional"))
      (node (ref "U2") (pin "8") (pinfunction "OUTC_8") (pintype "output"))
      (node (ref "U2") (pin "9") (pinfunction "-INC_9") (pintype "input"))
    )
    (net (code "72") (name "Net-(U2--IND)") (class "Default")
      (node (ref "J9") (pin "3") (pinfunction "3_3") (pintype "bidirectional"))
      (node (ref "U2") (pin "13") (pinfunction "-IND_13") (pintype "input"))
      (node (ref "U2") (pin "14") (pinfunction "OUTD_14") (pintype "output"))
    )
    (net (code "73") (name "Net-(U3--INC)") (class "Default")
      (node (ref "J7") (pin "4") (pinfunction "4_4") (pintype "bidirectional"))
      (node (ref "U3") (pin "8") (pinfunction "OUTC_8") (pintype "output"))
      (node (ref "U3") (pin "9") (pinfunction "-INC_9") (pintype "input"))
    )
    (net (code "74") (name "Net-(U3--IND)") (class "Default")
      (node (ref "J7") (pin "3") (pinfunction "3_3") (pintype "bidirectional"))
      (node (ref "U3") (pin "13") (pinfunction "-IND_13") (pintype "input"))
      (node (ref "U3") (pin "14") (pinfunction "OUTD_14") (pintype "output"))
    )
    (net (code "75") (name "Net-(U6-B1)") (class "Default")
      (node (ref "J23") (pin "1") (pinfunction "1_1") (pintype "passive"))
      (node (ref "U6") (pin "3") (pinfunction "B1_3") (pintype "bidirectional"))
    )
    (net (code "76") (name "Net-(U6-B2)") (class "Default")
      (node (ref "J23") (pin "2") (pinfunction "2_2") (pintype "passive"))
      (node (ref "U6") (pin "6") (pinfunction "B2_6") (pintype "bidirectional"))
    )
    (net (code "77") (name "Net-(U6-B3)") (class "Default")
      (node (ref "J23") (pin "3") (pinfunction "3_3") (pintype "passive"))
      (node (ref "U6") (pin "10") (pinfunction "B3_10") (pintype "bidirectional"))
    )
    (net (code "78") (name "Net-(U6-S)") (class "Default")
      (node (ref "J2") (pin "2") (pinfunction "2_2") (pintype "passive"))
      (node (ref "R31") (pin "1") (pinfunction "1_1") (pintype "passive"))
      (node (ref "U6") (pin "1") (pinfunction "S_1") (pintype "bidirectional"))
      (node (ref "U7") (pin "1") (pinfunction "S_1") (pintype "bidirectional"))
    )
    (net (code "79") (name "Net-(U6-Y1)") (class "Default")
      (node (ref "R7") (pin "1") (pinfunction "1_1") (pintype "passive"))
      (node (ref "U6") (pin "4") (pinfunction "Y1_4") (pintype "bidirectional"))
    )
    (net (code "80") (name "Net-(U6-Y2)") (class "Default")
      (node (ref "R10") (pin "1") (pinfunction "1_1") (pintype "passive"))
      (node (ref "U6") (pin "7") (pinfunction "Y2_7") (pintype "bidirectional"))
    )
    (net (code "81") (name "Net-(U6-Y3)") (class "Default")
      (node (ref "R8") (pin "1") (pinfunction "1_1") (pintype "passive"))
      (node (ref "U6") (pin "9") (pinfunction "Y3_9") (pintype "bidirectional"))
    )
    (net (code "82") (name "Net-(U7-B1)") (class "Default")
      (node (ref "J23") (pin "5") (pinfunction "5_5") (pintype "passive"))
      (node (ref "U7") (pin "3") (pinfunction "B1_3") (pintype "bidirectional"))
    )
    (net (code "83") (name "Net-(U7-B2)") (class "Default")
      (node (ref "J23") (pin "6") (pinfunction "6_6") (pintype "passive"))
      (node (ref "U7") (pin "6") (pinfunction "B2_6") (pintype "bidirectional"))
    )
    (net (code "84") (name "Net-(U7-B3)") (class "Default")
      (node (ref "J23") (pin "7") (pinfunction "7_7") (pintype "passive"))
      (node (ref "U7") (pin "10") (pinfunction "B3_10") (pintype "bidirectional"))
    )
    (net (code "85") (name "Net-(U7-Y1)") (class "Default")
      (node (ref "R11") (pin "1") (pinfunction "1_1") (pintype "passive"))
      (node (ref "U7") (pin "4") (pinfunction "Y1_4") (pintype "bidirectional"))
    )
    (net (code "86") (name "Net-(U7-Y2)") (class "Default")
      (node (ref "R12") (pin "1") (pinfunction "1_1") (pintype "passive"))
      (node (ref "U7") (pin "7") (pinfunction "Y2_7") (pintype "bidirectional"))
    )
    (net (code "87") (name "Net-(U7-Y3)") (class "Default")
      (node (ref "R14") (pin "1") (pinfunction "1_1") (pintype "passive"))
      (node (ref "U7") (pin "9") (pinfunction "Y3_9") (pintype "bidirectional"))
    )
    (net (code "88") (name "unconnected-(IC3-1A-Pad1)") (class "Default")
      (node (ref "IC3") (pin "1") (pinfunction "1A_1") (pintype "bidirectional"))
    )
    (net (code "89") (name "unconnected-(IC3-1Y-Pad2)") (class "Default")
      (node (ref "IC3") (pin "2") (pinfunction "1Y_2") (pintype "bidirectional"))
    )
    (net (code "90") (name "unconnected-(IC3-2A-Pad3)") (class "Default")
      (node (ref "IC3") (pin "3") (pinfunction "2A_3") (pintype "bidirectional"))
    )
    (net (code "91") (name "unconnected-(IC3-2Y-Pad4)") (class "Default")
      (node (ref "IC3") (pin "4") (pinfunction "2Y_4") (pintype "bidirectional"))
    )
    (net (code "92") (name "unconnected-(IC3-3A-Pad5)") (class "Default")
      (node (ref "IC3") (pin "5") (pinfunction "3A_5") (pintype "bidirectional"))
    )
    (net (code "93") (name "unconnected-(IC3-3Y-Pad6)") (class "Default")
      (node (ref "IC3") (pin "6") (pinfunction "3Y_6") (pintype "bidirectional"))
    )
    (net (code "94") (name "unconnected-(IC3-5A-Pad11)") (class "Default")
      (node (ref "IC3") (pin "11") (pinfunction "5A_11") (pintype "bidirectional"))
    )
    (net (code "95") (name "unconnected-(IC3-5Y-Pad10)") (class "Default")
      (node (ref "IC3") (pin "10") (pinfunction "5Y_10") (pintype "bidirectional"))
    )
    (net (code "96") (name "unconnected-(IC4-N{slash}C_1-Pad1)") (class "Default")
      (node (ref "IC4") (pin "1") (pinfunction "N/C_1_1") (pintype "bidirectional"))
    )
    (net (code "97") (name "unconnected-(IC4-N{slash}C_2-Pad5)") (class "Default")
      (node (ref "IC4") (pin "5") (pinfunction "N/C_2_5") (pintype "bidirectional"))
    )
    (net (code "98") (name "unconnected-(IC4-N{slash}C_3-Pad8)") (class "Default")
      (node (ref "IC4") (pin "8") (pinfunction "N/C_3_8") (pintype "bidirectional"))
    )
    (net (code "99") (name "unconnected-(IC5-N{slash}C_1-Pad1)") (class "Default")
      (node (ref "IC5") (pin "1") (pinfunction "N/C_1_1") (pintype "bidirectional"))
    )
    (net (code "100") (name "unconnected-(IC5-N{slash}C_2-Pad5)") (class "Default")
      (node (ref "IC5") (pin "5") (pinfunction "N/C_2_5") (pintype "bidirectional"))
    )
    (net (code "101") (name "unconnected-(IC5-N{slash}C_3-Pad8)") (class "Default")
      (node (ref "IC5") (pin "8") (pinfunction "N/C_3_8") (pintype "bidirectional"))
    )
    (net (code "102") (name "unconnected-(J1-Pad1)") (class "Default")
      (node (ref "J1") (pin "1") (pinfunction "1_1") (pintype "passive"))
    )
    (net (code "103") (name "unconnected-(J15-Pad1)") (class "Default")
      (node (ref "J15") (pin "1") (pinfunction "1_1") (pintype "passive"))
    )
    (net (code "104") (name "unconnected-(J15-Pad2)") (class "Default")
      (node (ref "J15") (pin "2") (pinfunction "2_2") (pintype "passive"))
    )
    (net (code "105") (name "unconnected-(U1-PadCN11_1)") (class "Default")
      (node (ref "U1") (pin "CN11_1") (pinfunction "CN11_1_CN11_1") (pintype "passive"))
    )
    (net (code "106") (name "unconnected-(U1-PadCN11_2)") (class "Default")
      (node (ref "U1") (pin "CN11_2") (pinfunction "CN11_2_CN11_2") (pintype "passive"))
    )
    (net (code "107") (name "unconnected-(U1-PadCN12_1)") (class "Default")
      (node (ref "U1") (pin "CN12_1") (pinfunction "CN12_1_CN12_1") (pintype "passive"))
    )
    (net (code "108") (name "unconnected-(U1-PadCN12_2)") (class "Default")
      (node (ref "U1") (pin "CN12_2") (pinfunction "CN12_2_CN12_2") (pintype "passive"))
    )
    (net (code "109") (name "unconnected-(U1A-BOOT0-PadCN7_7)") (class "Default")
      (node (ref "U1") (pin "CN7_7") (pinfunction "BOOT0_CN7_7") (pintype "bidirectional"))
    )
    (net (code "110") (name "unconnected-(U1A-IOREF-PadCN7_12)") (class "Default")
      (node (ref "U1") (pin "CN7_12") (pinfunction "IOREF_CN7_12") (pintype "bidirectional"))
    )
    (net (code "111") (name "unconnected-(U1A-NC_9-PadCN7_9)") (class "Default")
      (node (ref "U1") (pin "CN7_9") (pinfunction "NC_9_CN7_9") (pintype "no_connect"))
    )
    (net (code "112") (name "unconnected-(U1A-NC_10_CN7-PadCN7_10)") (class "Default")
      (node (ref "U1") (pin "CN7_10") (pinfunction "NC_10_CN7_CN7_10") (pintype "no_connect"))
    )
    (net (code "113") (name "unconnected-(U1A-NC_11-PadCN7_11)") (class "Default")
      (node (ref "U1") (pin "CN7_11") (pinfunction "NC_11_CN7_11") (pintype "no_connect"))
    )
    (net (code "114") (name "unconnected-(U1A-NC_26-PadCN7_26)") (class "Default")
      (node (ref "U1") (pin "CN7_26") (pinfunction "NC_26_CN7_26") (pintype "no_connect"))
    )
    (net (code "115") (name "unconnected-(U1A-PA13-PadCN7_13)") (class "Default")
      (node (ref "U1") (pin "CN7_13") (pinfunction "PA13_CN7_13") (pintype "bidirectional"))
    )
    (net (code "116") (name "unconnected-(U1A-PA14-PadCN7_15)") (class "Default")
      (node (ref "U1") (pin "CN7_15") (pinfunction "PA14_CN7_15") (pintype "bidirectional"))
    )
    (net (code "117") (name "unconnected-(U1A-PA15-PadCN7_17)") (class "Default")
      (node (ref "U1") (pin "CN7_17") (pinfunction "PA15_CN7_17") (pintype "bidirectional"))
    )
    (net (code "118") (name "unconnected-(U1A-PC10-PadCN7_1)") (class "Default")
      (node (ref "U1") (pin "CN7_1") (pinfunction "PC10_CN7_1") (pintype "bidirectional"))
    )
    (net (code "119") (name "unconnected-(U1A-PC14-PadCN7_25)") (class "Default")
      (node (ref "U1") (pin "CN7_25") (pinfunction "PC14_CN7_25") (pintype "bidirectional"))
    )
    (net (code "120") (name "unconnected-(U1A-PC15-PadCN7_27)") (class "Default")
      (node (ref "U1") (pin "CN7_27") (pinfunction "PC15_CN7_27") (pintype "bidirectional"))
    )
    (net (code "121") (name "unconnected-(U1A-PD2-PadCN7_4)") (class "Default")
      (node (ref "U1") (pin "CN7_4") (pinfunction "PD2_CN7_4") (pintype "bidirectional"))
    )
    (net (code "122") (name "unconnected-(U1A-PH0-PadCN7_29)") (class "Default")
      (node (ref "U1") (pin "CN7_29") (pinfunction "PH0_CN7_29") (pintype "bidirectional"))
    )
    (net (code "123") (name "unconnected-(U1A-PH1-PadCN7_31)") (class "Default")
      (node (ref "U1") (pin "CN7_31") (pinfunction "PH1_CN7_31") (pintype "bidirectional"))
    )
    (net (code "124") (name "unconnected-(U1A-RESET-PadCN7_14)") (class "Default")
      (node (ref "U1") (pin "CN7_14") (pinfunction "RESET_CN7_14") (pintype "bidirectional"))
    )
    (net (code "125") (name "unconnected-(U1A-VIN-PadCN7_24)") (class "Default")
      (node (ref "U1") (pin "CN7_24") (pinfunction "VIN_CN7_24") (pintype "bidirectional"))
    )
    (net (code "126") (name "unconnected-(U1B-NC_10_CN10-PadCN10_10)") (class "Default")
      (node (ref "U1") (pin "CN10_10") (pinfunction "NC_10_CN10_CN10_10") (pintype "no_connect"))
    )
    (net (code "127") (name "unconnected-(U1B-NC_18-PadCN10_18)") (class "Default")
      (node (ref "U1") (pin "CN10_18") (pinfunction "NC_18_CN10_18") (pintype "no_connect"))
    )
    (net (code "128") (name "unconnected-(U1B-NC_36-PadCN10_36)") (class "Default")
      (node (ref "U1") (pin "CN10_36") (pinfunction "NC_36_CN10_36") (pintype "no_connect"))
    )
    (net (code "129") (name "unconnected-(U1B-NC_38-PadCN10_38)") (class "Default")
      (node (ref "U1") (pin "CN10_38") (pinfunction "NC_38_CN10_38") (pintype "no_connect"))
    )
    (net (code "130") (name "unconnected-(U1B-PA2-PadCN10_35)") (class "Default")
      (node (ref "U1") (pin "CN10_35") (pinfunction "PA2_CN10_35") (pintype "bidirectional"))
    )
    (net (code "131") (name "unconnected-(U1B-PA3-PadCN10_37)") (class "Default")
      (node (ref "U1") (pin "CN10_37") (pinfunction "PA3_CN10_37") (pintype "bidirectional"))
    )
    (net (code "132") (name "unconnected-(U1B-PA5-PadCN10_11)") (class "Default")
      (node (ref "U1") (pin "CN10_11") (pinfunction "PA5_CN10_11") (pintype "bidirectional"))
    )
    (net (code "133") (name "unconnected-(U1B-PA9-PadCN10_21)") (class "Default")
      (node (ref "U1") (pin "CN10_21") (pinfunction "PA9_CN10_21") (pintype "bidirectional"))
    )
    (net (code "134") (name "unconnected-(U1B-PA10-PadCN10_33)") (class "Default")
      (node (ref "U1") (pin "CN10_33") (pinfunction "PA10_CN10_33") (pintype "bidirectional"))
    )
    (net (code "135") (name "unconnected-(U1B-PA11-PadCN10_14)") (class "Default")
      (node (ref "U1") (pin "CN10_14") (pinfunction "PA11_CN10_14") (pintype "bidirectional"))
    )
    (net (code "136") (name "unconnected-(U1B-PA12-PadCN10_12)") (class "Default")
      (node (ref "U1") (pin "CN10_12") (pinfunction "PA12_CN10_12") (pintype "bidirectional"))
    )
    (net (code "137") (name "unconnected-(U1B-PB8-PadCN10_3)") (class "Default")
      (node (ref "U1") (pin "CN10_3") (pinfunction "PB8_CN10_3") (pintype "bidirectional"))
    )
    (net (code "138") (name "unconnected-(U1B-PB9-PadCN10_5)") (class "Default")
      (node (ref "U1") (pin "CN10_5") (pinfunction "PB9_CN10_5") (pintype "bidirectional"))
    )
    (net (code "139") (name "unconnected-(U1B-PB12-PadCN10_16)") (class "Default")
      (node (ref "U1") (pin "CN10_16") (pinfunction "PB12_CN10_16") (pintype "bidirectional"))
    )
    (net (code "140") (name "unconnected-(U1B-PB13-PadCN10_30)") (class "Default")
      (node (ref "U1") (pin "CN10_30") (pinfunction "PB13_CN10_30") (pintype "bidirectional"))
    )
    (net (code "141") (name "unconnected-(U1B-PB14-PadCN10_28)") (class "Default")
      (node (ref "U1") (pin "CN10_28") (pinfunction "PB14_CN10_28") (pintype "bidirectional"))
    )
    (net (code "142") (name "unconnected-(U2-+INA_-Pad3)") (class "Default")
      (node (ref "U2") (pin "3") (pinfunction "+INA__3") (pintype "input"))
    )
    (net (code "143") (name "unconnected-(U2-+INB-Pad5)") (class "Default")
      (node (ref "U2") (pin "5") (pinfunction "+INB_5") (pintype "input"))
    )
    (net (code "144") (name "unconnected-(U2--INA-Pad2)") (class "Default")
      (node (ref "U2") (pin "2") (pinfunction "-INA_2") (pintype "input"))
    )
    (net (code "145") (name "unconnected-(U2--INB-Pad6)") (class "Default")
      (node (ref "U2") (pin "6") (pinfunction "-INB_6") (pintype "input"))
    )
    (net (code "146") (name "unconnected-(U2-OUTA-Pad1)") (class "Default")
      (node (ref "U2") (pin "1") (pinfunction "OUTA_1") (pintype "output"))
    )
    (net (code "147") (name "unconnected-(U2-OUTB-Pad7)") (class "Default")
      (node (ref "U2") (pin "7") (pinfunction "OUTB_7") (pintype "output"))
    )
    (net (code "148") (name "unconnected-(U3-+INA_-Pad3)") (class "Default")
      (node (ref "U3") (pin "3") (pinfunction "+INA__3") (pintype "input"))
    )
    (net (code "149") (name "unconnected-(U3-+INB-Pad5)") (class "Default")
      (node (ref "U3") (pin "5") (pinfunction "+INB_5") (pintype "input"))
    )
    (net (code "150") (name "unconnected-(U3--INA-Pad2)") (class "Default")
      (node (ref "U3") (pin "2") (pinfunction "-INA_2") (pintype "input"))
    )
    (net (code "151") (name "unconnected-(U3--INB-Pad6)") (class "Default")
      (node (ref "U3") (pin "6") (pinfunction "-INB_6") (pintype "input"))
    )
    (net (code "152") (name "unconnected-(U3-OUTA-Pad1)") (class "Default")
      (node (ref "U3") (pin "1") (pinfunction "OUTA_1") (pintype "output"))
    )
    (net (code "153") (name "unconnected-(U3-OUTB-Pad7)") (class "Default")
      (node (ref "U3") (pin "7") (pinfunction "OUTB_7") (pintype "output"))
    )
    (net (code "154") (name "unconnected-(U6-A4-Pad14)") (class "Default")
      (node (ref "U6") (pin "14") (pinfunction "A4_14") (pintype "bidirectional"))
    )
    (net (code "155") (name "unconnected-(U6-B4-Pad13)") (class "Default")
      (node (ref "U6") (pin "13") (pinfunction "B4_13") (pintype "bidirectional"))
    )
    (net (code "156") (name "unconnected-(U6-Y4-Pad12)") (class "Default")
      (node (ref "U6") (pin "12") (pinfunction "Y4_12") (pintype "bidirectional"))
    )
    (net (code "157") (name "unconnected-(U7-A4-Pad14)") (class "Default")
      (node (ref "U7") (pin "14") (pinfunction "A4_14") (pintype "bidirectional"))
    )
    (net (code "158") (name "unconnected-(U7-B4-Pad13)") (class "Default")
      (node (ref "U7") (pin "13") (pinfunction "B4_13") (pintype "bidirectional"))
    )
    (net (code "159") (name "unconnected-(U7-Y4-Pad12)") (class "Default")
      (node (ref "U7") (pin "12") (pinfunction "Y4_12") (pintype "bidirectional"))
    )
  )
)
